# main.net
KiCad netlist of a schematic drawn in Altium Designer
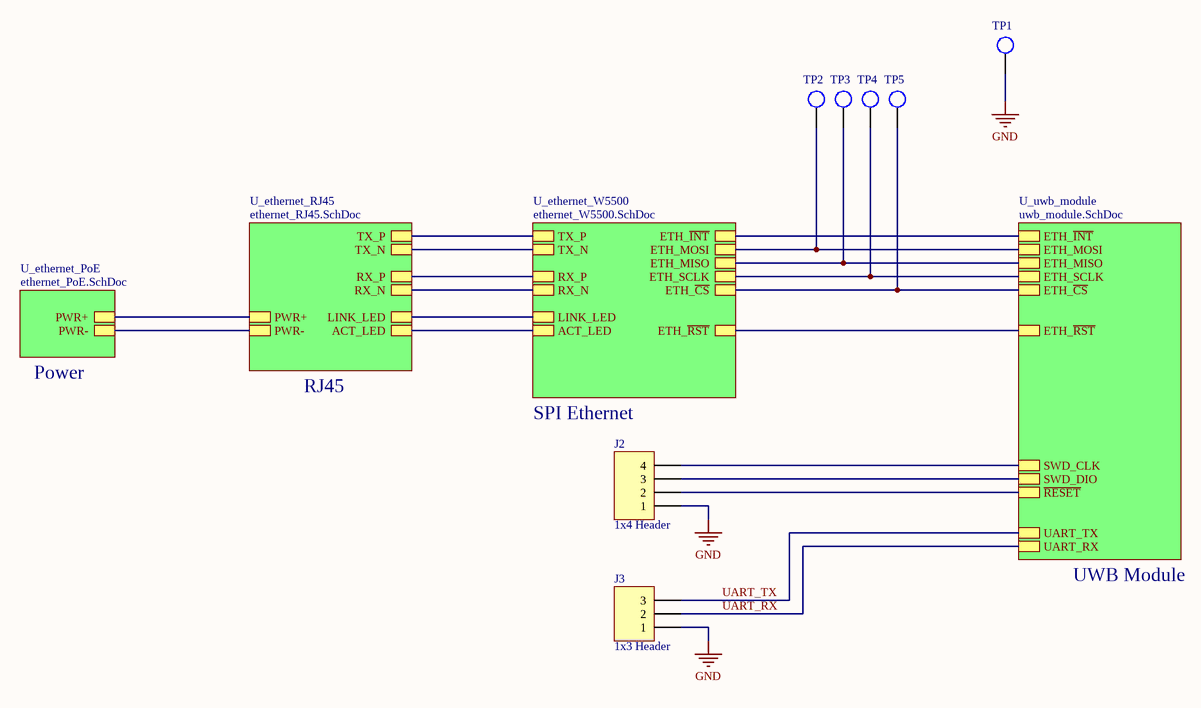
[diagram p0: main.SchDoc]

(export (version "E")
  (design (tool "Eeschema 10.0.6"))
  (components
    (comp (ref "J2")
      (value "1x4 Header")
      (footprint "HDR1X4")
      (description "1x4 Pin Header")
      (libsource (lib "GeneralConnectors") (part "1x4 Header"))
    )
    (comp (ref "J3")
      (value "1x3 Header")
      (footprint "HDR1X3")
      (description "1x3 Pin Header")
      (libsource (lib "GeneralConnectors") (part "1x3 Header"))
    )
    (comp (ref "TP1")
      (value "Test Point")
      (footprint "Test Point")
      (libsource (lib "General") (part "Test Point"))
    )
    (comp (ref "TP2")
      (value "Test Point")
      (footprint "Test Point")
      (libsource (lib "General") (part "Test Point"))
    )
    (comp (ref "TP3")
      (value "Test Point")
      (footprint "Test Point")
      (libsource (lib "General") (part "Test Point"))
    )
    (comp (ref "TP4")
      (value "Test Point")
      (footprint "Test Point")
      (libsource (lib "General") (part "Test Point"))
    )
    (comp (ref "TP5")
      (value "Test Point")
      (footprint "Test Point")
      (libsource (lib "General") (part "Test Point"))
    )
  )
  (nets
    (net (code "2") (name "/ETH_MISO") (class "Default")
      (node (ref "TP3") (pin "1") (pinfunction "0_1") (pintype "passive"))
    )
    (net (code "3") (name "/ETH_MOSI") (class "Default")
      (node (ref "TP2") (pin "1") (pinfunction "0_1") (pintype "passive"))
    )
    (net (code "4") (name "/ETH_SCLK") (class "Default")
      (node (ref "TP4") (pin "1") (pinfunction "0_1") (pintype "passive"))
    )
    (net (code "5") (name "/ETH_~{CS}") (class "Default")
      (node (ref "TP5") (pin "1") (pinfunction "0_1") (pintype "passive"))
    )
    (net (code "13") (name "/SWD_CLK") (class "Default")
      (node (ref "J2") (pin "4") (pinfunction "4_4") (pintype "passive"))
    )
    (net (code "14") (name "/SWD_DIO") (class "Default")
      (node (ref "J2") (pin "3") (pinfunction "3_3") (pintype "passive"))
    )
    (net (code "17") (name "/UART_RX") (class "Default")
      (node (ref "J3") (pin "2") (pinfunction "2_2") (pintype "passive"))
    )
    (net (code "18") (name "/UART_TX") (class "Default")
      (node (ref "J3") (pin "3") (pinfunction "3_3") (pintype "passive"))
    )
    (net (code "19") (name "/~{RESET}") (class "Default")
      (node (ref "J2") (pin "2") (pinfunction "2_2") (pintype "passive"))
    )
    (net (code "20") (name "GND") (class "Default")
      (node (ref "J2") (pin "1") (pinfunction "1_1") (pintype "passive"))
      (node (ref "J3") (pin "1") (pinfunction "1_1") (pintype "passive"))
      (node (ref "TP1") (pin "1") (pinfunction "0_1") (pintype "passive"))
    )
  )
)
